# Sheet1.net
KiCad netlist of a schematic drawn in Altium Designer
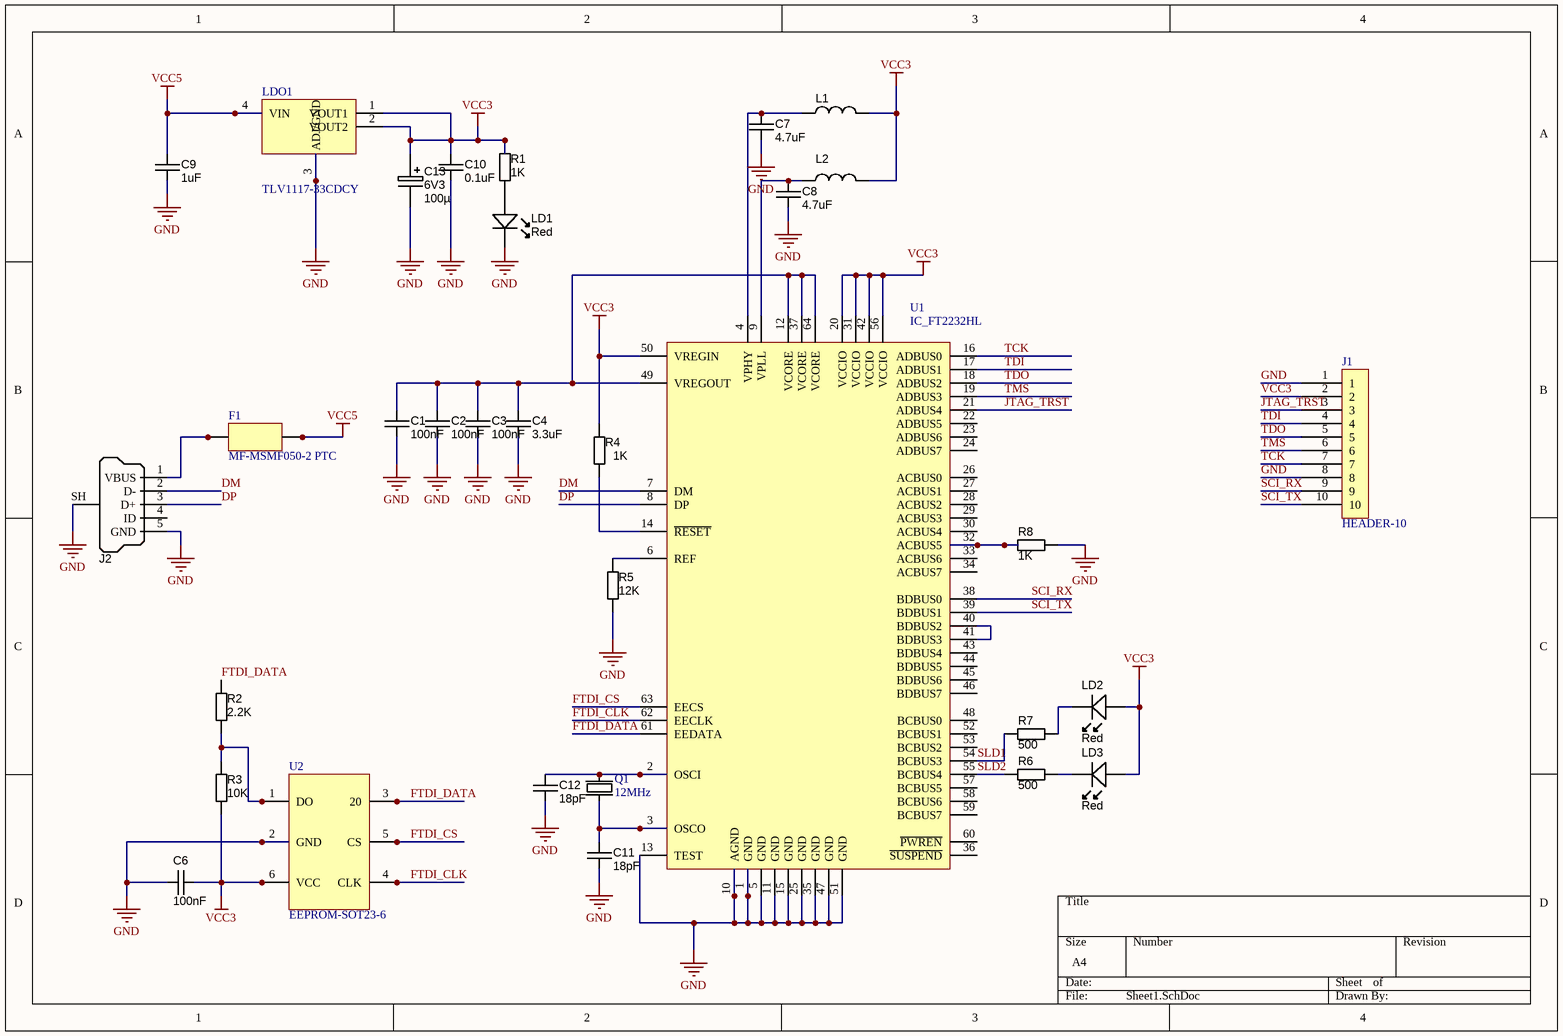
[diagram p0: Sheet1.SchDoc]

(export (version "E")
  (design (tool "Eeschema 10.0.6"))
  (components
    (comp (ref "C1")
      (value "100nF")
      (footprint "CAPC1608X90N")
      (description "Capacitor SMD Cer 39pF 1% 100V NP0 0603")
      (fields (field (name "TOLERANCE") "±1%"))
      (libsource (lib "PBL - Capacitors") (part "CAPC_39p_0603_NP0_100V_1%"))
    )
    (comp (ref "C2")
      (value "100nF")
      (footprint "CAPC1608X90N")
      (description "Capacitor SMD Cer 39pF 1% 100V NP0 0603")
      (fields (field (name "TOLERANCE") "±1%"))
      (libsource (lib "PBL - Capacitors") (part "CAPC_39p_0603_NP0_100V_1%"))
    )
    (comp (ref "C3")
      (value "100nF")
      (footprint "CAPC1608X90N")
      (description "Capacitor SMD Cer 39pF 1% 100V NP0 0603")
      (fields (field (name "TOLERANCE") "±1%"))
      (libsource (lib "PBL - Capacitors") (part "CAPC_39p_0603_NP0_100V_1%"))
    )
    (comp (ref "C4")
      (value "3.3uF")
      (footprint "CAPC1608X90N")
      (description "Capacitor SMD Cer 39pF 1% 100V NP0 0603")
      (fields (field (name "TOLERANCE") "±1%"))
      (libsource (lib "PBL - Capacitors") (part "CAPC_39p_0603_NP0_100V_1%"))
    )
    (comp (ref "C6")
      (value "100nF")
      (footprint "CAPC1608X90N")
      (description "Capacitor SMD Cer 39pF 1% 100V NP0 0603")
      (fields (field (name "TOLERANCE") "±1%"))
      (libsource (lib "PBL - Capacitors") (part "CAPC_39p_0603_NP0_100V_1%"))
    )
    (comp (ref "C7")
      (value "4.7uF")
      (footprint "CAPC1608X90N")
      (description "Capacitor SMD Cer 39pF 1% 100V NP0 0603")
      (fields (field (name "TOLERANCE") "±1%"))
      (libsource (lib "PBL - Capacitors") (part "CAPC_39p_0603_NP0_100V_1%"))
    )
    (comp (ref "C8")
      (value "4.7uF")
      (footprint "CAPC1608X90N")
      (description "Capacitor SMD Cer 39pF 1% 100V NP0 0603")
      (fields (field (name "TOLERANCE") "±1%"))
      (libsource (lib "PBL - Capacitors") (part "CAPC_39p_0603_NP0_100V_1%"))
    )
    (comp (ref "C9")
      (value "1uF")
      (footprint "CAPC1608X90N")
      (description "Capacitor SMD Cer 39pF 1% 100V NP0 0603")
      (fields (field (name "TOLERANCE") "±1%"))
      (libsource (lib "PBL - Capacitors") (part "CAPC_39p_0603_NP0_100V_1%"))
    )
    (comp (ref "C10")
      (value "0.1uF")
      (footprint "CAPC1608X90N")
      (description "Capacitor SMD Cer 39pF 1% 100V NP0 0603")
      (fields (field (name "TOLERANCE") "±1%"))
      (libsource (lib "PBL - Capacitors") (part "CAPC_39p_0603_NP0_100V_1%"))
    )
    (comp (ref "C11")
      (value "18pF")
      (footprint "CAPC1608X90N")
      (description "Capacitor SMD Cer 39pF 1% 100V NP0 0603")
      (fields (field (name "TOLERANCE") "±1%"))
      (libsource (lib "PBL - Capacitors") (part "CAPC_39p_0603_NP0_100V_1%"))
    )
    (comp (ref "C12")
      (value "18pF")
      (footprint "CAPC1608X90N")
      (description "Capacitor SMD Cer 39pF 1% 100V NP0 0603")
      (fields (field (name "TOLERANCE") "±1%"))
      (libsource (lib "PBL - Capacitors") (part "CAPC_39p_0603_NP0_100V_1%"))
    )
    (comp (ref "C13")
      (value "100µ")
      (footprint "CAPMP3528X210N")
      (description "Capacitor SMD Tantalum 100uF 20% 6.3V 1210")
      (fields (field (name "TOLERANCE") "±20%") (field (name "RATINGS") "6V3"))
      (libsource (lib "PBL - Capacitors") (part "CAPT_100u_1210_6V3"))
    )
    (comp (ref "F1")
      (value "MF-MSMF050-2 PTC")
      (footprint "PTC-1218")
      (libsource (lib "power") (part "MF-MSMF050-2 PTC"))
    )
    (comp (ref "J1")
      (value "HEADER-10")
      (footprint "MICRO-MATCH-10")
      (libsource (lib "connectors") (part "HEADER-10"))
    )
    (comp (ref "J2")
      (value "USB Micro Type B (recommended if hand soldering)")
      (footprint "USB_Micro-B_FCI_SMD")
      (description "Connector SMD-THD USB Micro Type B middle mount")
      (libsource (lib "PBL - Connectors") (part "USB_Micro_TypeB_FCI"))
    )
    (comp (ref "L1")
      (value "120R @ 100 MHz")
      (footprint "INDC1608N")
      (description "Ferrite bead 120 Ohm at 100 MHz 2A 0603 SMD")
      (libsource (lib "PBL - Inductors") (part "FERRITE_120R-100MHz_0603"))
    )
    (comp (ref "L2")
      (value "120R @ 100 MHz")
      (footprint "INDC1608N")
      (description "Ferrite bead 120 Ohm at 100 MHz 2A 0603 SMD")
      (libsource (lib "PBL - Inductors") (part "FERRITE_120R-100MHz_0603"))
    )
    (comp (ref "LD1")
      (value "Red")
      (footprint "LED-0603-RED")
      (description "LED 0603 SMD Hyper Red 630nm 220mcd 20mA")
      (libsource (lib "PBL - Light Sources") (part "LED_SMD_Red_0603_220mcd"))
    )
    (comp (ref "LD2")
      (value "Red")
      (footprint "LED-0603-RED")
      (description "LED 0603 SMD Hyper Red 630nm 220mcd 20mA")
      (libsource (lib "PBL - Light Sources") (part "LED_SMD_Red_0603_220mcd"))
    )
    (comp (ref "LD3")
      (value "Red")
      (footprint "LED-0603-RED")
      (description "LED 0603 SMD Hyper Red 630nm 220mcd 20mA")
      (libsource (lib "PBL - Light Sources") (part "LED_SMD_Red_0603_220mcd"))
    )
    (comp (ref "LDO1")
      (value "TLV1117-33CDCY")
      (footprint "SOT223")
      (libsource (lib "texas_instruments") (part "TLV1117-33CDCY"))
    )
    (comp (ref "Q1") (value "12MHz") (footprint "XTAL-5x3.2") (libsource (lib "misc") (part "XTAL_5x3.2")))
    (comp (ref "R1")
      (value "1K")
      (footprint "RESC1608X55N")
      (description "Resistor SMD chip 1k Ohm 0.1W 5% 0603")
      (fields (field (name "TOLERANCE") "±5%") (field (name "Comment") "Thick Film"))
      (libsource (lib "") (part "RES_1K_0603_5%_2"))
    )
    (comp (ref "R2")
      (value "2.2K")
      (footprint "RESC1608X55N")
      (description "Resistor SMD chip 1k Ohm 0.1W 5% 0603")
      (fields (field (name "TOLERANCE") "±5%") (field (name "Comment") "Thick Film"))
      (libsource (lib "") (part "RES_1K_0603_5%_2"))
    )
    (comp (ref "R3")
      (value "10K")
      (footprint "RESC1608X55N")
      (description "Resistor SMD chip 1k Ohm 0.1W 5% 0603")
      (fields (field (name "TOLERANCE") "±5%") (field (name "Comment") "Thick Film"))
      (libsource (lib "") (part "RES_1K_0603_5%_2"))
    )
    (comp (ref "R4")
      (value "1K")
      (footprint "RESC1608X55N")
      (description "Resistor SMD chip 1k Ohm 0.1W 5% 0603")
      (fields (field (name "TOLERANCE") "±5%"))
      (libsource (lib "") (part "RES_1K_0603_5%_1"))
    )
    (comp (ref "R5")
      (value "12K")
      (footprint "RESC1608X55N")
      (description "Resistor SMD chip 1k Ohm 0.1W 5% 0603")
      (fields (field (name "TOLERANCE") "±5%") (field (name "Comment") "Thick Film"))
      (libsource (lib "") (part "RES_1K_0603_5%_1"))
    )
    (comp (ref "R6")
      (value "500")
      (footprint "RESC1608X55N")
      (description "Resistor SMD chip 1k Ohm 0.1W 5% 0603")
      (fields (field (name "TOLERANCE") "±5%") (field (name "Comment") "Thick Film"))
      (libsource (lib "PBL - Resistors") (part "RES_1K_0603_5%"))
    )
    (comp (ref "R7")
      (value "500")
      (footprint "RESC1608X55N")
      (description "Resistor SMD chip 1k Ohm 0.1W 5% 0603")
      (fields (field (name "TOLERANCE") "±5%") (field (name "Comment") "Thick Film"))
      (libsource (lib "PBL - Resistors") (part "RES_1K_0603_5%"))
    )
    (comp (ref "R8")
      (value "1K")
      (footprint "RESC1608X55N")
      (description "Resistor SMD chip 1k Ohm 0.1W 5% 0603")
      (fields (field (name "TOLERANCE") "±5%") (field (name "Comment") "Thick Film"))
      (libsource (lib "PBL - Resistors") (part "RES_1K_0603_5%"))
    )
    (comp (ref "U1")
      (value "IC_FT2232HL")
      (footprint "LQFP-64")
      (description "Dual High Speed USB to Multipurpose UART/FIFO")
      (libsource (lib "FTDI_SCH_Public") (part "IC_FT2232HL"))
    )
    (comp (ref "U2")
      (value "EEPROM-SOT23-6")
      (footprint "SOT23-6-EEPROM")
      (libsource (lib "misc") (part "EEPROM-SOT23-6"))
    )
  )
  (nets
    (net (code "1") (name "/DM") (class "Default")
      (node (ref "J2") (pin "2") (pinfunction "D-_2") (pintype "passive"))
      (node (ref "U1") (pin "7") (pinfunction "DM_7") (pintype "passive"))
    )
    (net (code "2") (name "/DP") (class "Default")
      (node (ref "J2") (pin "3") (pinfunction "D+_3") (pintype "passive"))
      (node (ref "U1") (pin "8") (pinfunction "DP_8") (pintype "passive"))
    )
    (net (code "3") (name "/FTDI_CLK") (class "Default")
      (node (ref "U1") (pin "62") (pinfunction "EECLK_62") (pintype "passive"))
      (node (ref "U2") (pin "4") (pinfunction "CLK_4") (pintype "passive"))
    )
    (net (code "4") (name "/FTDI_CS") (class "Default")
      (node (ref "U1") (pin "63") (pinfunction "EECS_63") (pintype "passive"))
      (node (ref "U2") (pin "5") (pinfunction "CS_5") (pintype "passive"))
    )
    (net (code "5") (name "/FTDI_DATA") (class "Default")
      (node (ref "R2") (pin "1") (pinfunction "1_1") (pintype "passive"))
      (node (ref "U1") (pin "61") (pinfunction "EEDATA_61") (pintype "passive"))
      (node (ref "U2") (pin "3") (pinfunction "20_3") (pintype "passive"))
    )
    (net (code "6") (name "/JTAG_TRST") (class "Default")
      (node (ref "J1") (pin "3") (pinfunction "3_3") (pintype "passive"))
      (node (ref "U1") (pin "21") (pinfunction "ADBUS4_21") (pintype "passive"))
    )
    (net (code "7") (name "/SCI_RX") (class "Default")
      (node (ref "J1") (pin "9") (pinfunction "9_9") (pintype "passive"))
      (node (ref "U1") (pin "38") (pinfunction "BDBUS0_38") (pintype "passive"))
    )
    (net (code "8") (name "/SCI_TX") (class "Default")
      (node (ref "J1") (pin "10") (pinfunction "10_10") (pintype "passive"))
      (node (ref "U1") (pin "39") (pinfunction "BDBUS1_39") (pintype "passive"))
    )
    (net (code "9") (name "/SLD1") (class "Default")
      (node (ref "R7") (pin "2") (pinfunction "2_2") (pintype "passive"))
      (node (ref "U1") (pin "54") (pinfunction "BCBUS3_54") (pintype "passive"))
    )
    (net (code "10") (name "/SLD2") (class "Default")
      (node (ref "R6") (pin "2") (pinfunction "2_2") (pintype "passive"))
      (node (ref "U1") (pin "55") (pinfunction "BCBUS4_55") (pintype "passive"))
    )
    (net (code "11") (name "/TCK") (class "Default")
      (node (ref "J1") (pin "7") (pinfunction "7_7") (pintype "passive"))
      (node (ref "U1") (pin "16") (pinfunction "ADBUS0_16") (pintype "passive"))
    )
    (net (code "12") (name "/TDI") (class "Default")
      (node (ref "J1") (pin "4") (pinfunction "4_4") (pintype "passive"))
      (node (ref "U1") (pin "17") (pinfunction "ADBUS1_17") (pintype "passive"))
    )
    (net (code "13") (name "/TDO") (class "Default")
      (node (ref "J1") (pin "5") (pinfunction "5_5") (pintype "passive"))
      (node (ref "U1") (pin "18") (pinfunction "ADBUS2_18") (pintype "passive"))
    )
    (net (code "14") (name "/TMS") (class "Default")
      (node (ref "J1") (pin "6") (pinfunction "6_6") (pintype "passive"))
      (node (ref "U1") (pin "19") (pinfunction "ADBUS3_19") (pintype "passive"))
    )
    (net (code "15") (name "GND") (class "Default")
      (node (ref "C1") (pin "2") (pintype "passive"))
      (node (ref "C10") (pin "2") (pintype "passive"))
      (node (ref "C11") (pin "2") (pintype "passive"))
      (node (ref "C12") (pin "1") (pintype "passive"))
      (node (ref "C13") (pin "2") (pintype "passive"))
      (node (ref "C2") (pin "2") (pintype "passive"))
      (node (ref "C3") (pin "2") (pintype "passive"))
      (node (ref "C4") (pin "2") (pintype "passive"))
      (node (ref "C6") (pin "1") (pintype "passive"))
      (node (ref "C7") (pin "2") (pintype "passive"))
      (node (ref "C8") (pin "2") (pintype "passive"))
      (node (ref "C9") (pin "2") (pintype "passive"))
      (node (ref "J1") (pin "1") (pinfunction "1_1") (pintype "passive"))
      (node (ref "J1") (pin "8") (pinfunction "8_8") (pintype "passive"))
      (node (ref "J2") (pin "5") (pinfunction "GND_5") (pintype "passive"))
      (node (ref "J2") (pin "SH") (pinfunction "Shell_SH") (pintype "passive"))
      (node (ref "LD1") (pin "K") (pinfunction "K_K") (pintype "passive"))
      (node (ref "LDO1") (pin "3") (pinfunction "ADJ/GND_3") (pintype "passive"))
      (node (ref "R5") (pin "1") (pinfunction "1_1") (pintype "passive"))
      (node (ref "R8") (pin "1") (pinfunction "1_1") (pintype "passive"))
      (node (ref "U1") (pin "1") (pinfunction "GND_1") (pintype "passive"))
      (node (ref "U1") (pin "10") (pinfunction "AGND_10") (pintype "passive"))
      (node (ref "U1") (pin "11") (pinfunction "GND_11") (pintype "passive"))
      (node (ref "U1") (pin "13") (pinfunction "TEST_13") (pintype "passive"))
      (node (ref "U1") (pin "15") (pinfunction "GND_15") (pintype "passive"))
      (node (ref "U1") (pin "25") (pinfunction "GND_25") (pintype "passive"))
      (node (ref "U1") (pin "35") (pinfunction "GND_35") (pintype "passive"))
      (node (ref "U1") (pin "47") (pinfunction "GND_47") (pintype "passive"))
      (node (ref "U1") (pin "5") (pinfunction "GND_5") (pintype "passive"))
      (node (ref "U1") (pin "51") (pinfunction "GND_51") (pintype "passive"))
      (node (ref "U2") (pin "2") (pinfunction "GND_2") (pintype "passive"))
    )
    (net (code "16") (name "Net-(F1-1)") (class "Default")
      (node (ref "F1") (pin "21") (pinfunction "1_21") (pintype "passive"))
      (node (ref "J2") (pin "1") (pinfunction "VBUS_1") (pintype "passive"))
    )
    (net (code "17") (name "Net-(LD1-PadA)") (class "Default")
      (node (ref "LD1") (pin "A") (pinfunction "A_A") (pintype "passive"))
      (node (ref "R1") (pin "2") (pinfunction "2_2") (pintype "passive"))
    )
    (net (code "18") (name "Net-(LD2-PadK)") (class "Default")
      (node (ref "LD2") (pin "K") (pinfunction "K_K") (pintype "passive"))
      (node (ref "R7") (pin "1") (pinfunction "1_1") (pintype "passive"))
    )
    (net (code "19") (name "Net-(LD3-PadK)") (class "Default")
      (node (ref "LD3") (pin "K") (pinfunction "K_K") (pintype "passive"))
      (node (ref "R6") (pin "1") (pinfunction "1_1") (pintype "passive"))
    )
    (net (code "20") (name "Net-(U1-ACBUS5)") (class "Default")
      (node (ref "R8") (pin "2") (pinfunction "2_2") (pintype "passive"))
      (node (ref "U1") (pin "32") (pinfunction "ACBUS5_32") (pintype "passive"))
    )
    (net (code "21") (name "Net-(U1-BDBUS2)") (class "Default")
      (node (ref "U1") (pin "40") (pinfunction "BDBUS2_40") (pintype "passive"))
      (node (ref "U1") (pin "41") (pinfunction "BDBUS3_41") (pintype "passive"))
    )
    (net (code "22") (name "Net-(U1-OSCI)") (class "Default")
      (node (ref "C12") (pin "2") (pintype "passive"))
      (node (ref "Q1") (pin "2") (pinfunction "2_2") (pintype "passive"))
      (node (ref "U1") (pin "2") (pinfunction "OSCI_2") (pintype "passive"))
    )
    (net (code "23") (name "Net-(U1-OSCO)") (class "Default")
      (node (ref "C11") (pin "1") (pintype "passive"))
      (node (ref "Q1") (pin "1") (pinfunction "1_1") (pintype "passive"))
      (node (ref "U1") (pin "3") (pinfunction "OSCO_3") (pintype "passive"))
    )
    (net (code "24") (name "Net-(U1-REF)") (class "Default")
      (node (ref "R5") (pin "2") (pinfunction "2_2") (pintype "passive"))
      (node (ref "U1") (pin "6") (pinfunction "REF_6") (pintype "passive"))
    )
    (net (code "25") (name "Net-(U1-VPHY)") (class "Default")
      (node (ref "C7") (pin "1") (pintype "passive"))
      (node (ref "L1") (pin "1") (pinfunction "1_1") (pintype "passive"))
      (node (ref "U1") (pin "4") (pinfunction "VPHY_4") (pintype "passive"))
    )
    (net (code "26") (name "Net-(U1-VPLL)") (class "Default")
      (node (ref "C8") (pin "1") (pintype "passive"))
      (node (ref "L2") (pin "1") (pinfunction "1_1") (pintype "passive"))
      (node (ref "U1") (pin "9") (pinfunction "VPLL_9") (pintype "passive"))
    )
    (net (code "27") (name "Net-(U1-VREGOUT)") (class "Default")
      (node (ref "C1") (pin "1") (pintype "passive"))
      (node (ref "C2") (pin "1") (pintype "passive"))
      (node (ref "C3") (pin "1") (pintype "passive"))
      (node (ref "C4") (pin "1") (pintype "passive"))
      (node (ref "U1") (pin "12") (pinfunction "VCORE_12") (pintype "passive"))
      (node (ref "U1") (pin "37") (pinfunction "VCORE_37") (pintype "passive"))
      (node (ref "U1") (pin "49") (pinfunction "VREGOUT_49") (pintype "passive"))
      (node (ref "U1") (pin "64") (pinfunction "VCORE_64") (pintype "passive"))
    )
    (net (code "28") (name "Net-(U1-~{RESET})") (class "Default")
      (node (ref "R4") (pin "1") (pinfunction "1_1") (pintype "passive"))
      (node (ref "U1") (pin "14") (pinfunction "~{RESET}_14") (pintype "passive"))
    )
    (net (code "29") (name "Net-(U2-DO)") (class "Default")
      (node (ref "R2") (pin "2") (pinfunction "2_2") (pintype "passive"))
      (node (ref "R3") (pin "1") (pinfunction "1_1") (pintype "passive"))
      (node (ref "U2") (pin "1") (pinfunction "DO_1") (pintype "passive"))
    )
    (net (code "30") (name "VCC3") (class "Default")
      (node (ref "C10") (pin "1") (pintype "passive"))
      (node (ref "C13") (pin "1") (pintype "passive"))
      (node (ref "C6") (pin "2") (pintype "passive"))
      (node (ref "J1") (pin "2") (pinfunction "2_2") (pintype "passive"))
      (node (ref "L1") (pin "2") (pinfunction "2_2") (pintype "passive"))
      (node (ref "L2") (pin "2") (pinfunction "2_2") (pintype "passive"))
      (node (ref "LD2") (pin "A") (pinfunction "A_A") (pintype "passive"))
      (node (ref "LD3") (pin "A") (pinfunction "A_A") (pintype "passive"))
      (node (ref "LDO1") (pin "1") (pinfunction "VOUT1_1") (pintype "passive"))
      (node (ref "LDO1") (pin "2") (pinfunction "VOUT2_2") (pintype "passive"))
      (node (ref "R1") (pin "1") (pinfunction "1_1") (pintype "passive"))
      (node (ref "R3") (pin "2") (pinfunction "2_2") (pintype "passive"))
      (node (ref "R4") (pin "2") (pinfunction "2_2") (pintype "passive"))
      (node (ref "U1") (pin "20") (pinfunction "VCCIO_20") (pintype "passive"))
      (node (ref "U1") (pin "31") (pinfunction "VCCIO_31") (pintype "passive"))
      (node (ref "U1") (pin "42") (pinfunction "VCCIO_42") (pintype "passive"))
      (node (ref "U1") (pin "50") (pinfunction "VREGIN_50") (pintype "passive"))
      (node (ref "U1") (pin "56") (pinfunction "VCCIO_56") (pintype "passive"))
      (node (ref "U2") (pin "6") (pinfunction "VCC_6") (pintype "passive"))
    )
    (net (code "31") (name "VCC5") (class "Default")
      (node (ref "C9") (pin "1") (pintype "passive"))
      (node (ref "F1") (pin "22") (pinfunction "2_22") (pintype "passive"))
      (node (ref "LDO1") (pin "4") (pinfunction "VIN_4") (pintype "passive"))
    )
    (net (code "32") (name "unconnected-(J2-ID-Pad4)") (class "Default")
      (node (ref "J2") (pin "4") (pinfunction "ID_4") (pintype "passive"))
    )
    (net (code "33") (name "unconnected-(U1-ACBUS0-Pad26)") (class "Default")
      (node (ref "U1") (pin "26") (pinfunction "ACBUS0_26") (pintype "passive"))
    )
    (net (code "34") (name "unconnected-(U1-ACBUS1-Pad27)") (class "Default")
      (node (ref "U1") (pin "27") (pinfunction "ACBUS1_27") (pintype "passive"))
    )
    (net (code "35") (name "unconnected-(U1-ACBUS2-Pad28)") (class "Default")
      (node (ref "U1") (pin "28") (pinfunction "ACBUS2_28") (pintype "passive"))
    )
    (net (code "36") (name "unconnected-(U1-ACBUS3-Pad29)") (class "Default")
      (node (ref "U1") (pin "29") (pinfunction "ACBUS3_29") (pintype "passive"))
    )
    (net (code "37") (name "unconnected-(U1-ACBUS4-Pad30)") (class "Default")
      (node (ref "U1") (pin "30") (pinfunction "ACBUS4_30") (pintype "passive"))
    )
    (net (code "38") (name "unconnected-(U1-ACBUS6-Pad33)") (class "Default")
      (node (ref "U1") (pin "33") (pinfunction "ACBUS6_33") (pintype "passive"))
    )
    (net (code "39") (name "unconnected-(U1-ACBUS7-Pad34)") (class "Default")
      (node (ref "U1") (pin "34") (pinfunction "ACBUS7_34") (pintype "passive"))
    )
    (net (code "40") (name "unconnected-(U1-ADBUS5-Pad22)") (class "Default")
      (node (ref "U1") (pin "22") (pinfunction "ADBUS5_22") (pintype "passive"))
    )
    (net (code "41") (name "unconnected-(U1-ADBUS6-Pad23)") (class "Default")
      (node (ref "U1") (pin "23") (pinfunction "ADBUS6_23") (pintype "passive"))
    )
    (net (code "42") (name "unconnected-(U1-ADBUS7-Pad24)") (class "Default")
      (node (ref "U1") (pin "24") (pinfunction "ADBUS7_24") (pintype "passive"))
    )
    (net (code "43") (name "unconnected-(U1-BCBUS0-Pad48)") (class "Default")
      (node (ref "U1") (pin "48") (pinfunction "BCBUS0_48") (pintype "passive"))
    )
    (net (code "44") (name "unconnected-(U1-BCBUS1-Pad52)") (class "Default")
      (node (ref "U1") (pin "52") (pinfunction "BCBUS1_52") (pintype "passive"))
    )
    (net (code "45") (name "unconnected-(U1-BCBUS2-Pad53)") (class "Default")
      (node (ref "U1") (pin "53") (pinfunction "BCBUS2_53") (pintype "passive"))
    )
    (net (code "46") (name "unconnected-(U1-BCBUS5-Pad57)") (class "Default")
      (node (ref "U1") (pin "57") (pinfunction "BCBUS5_57") (pintype "passive"))
    )
    (net (code "47") (name "unconnected-(U1-BCBUS6-Pad58)") (class "Default")
      (node (ref "U1") (pin "58") (pinfunction "BCBUS6_58") (pintype "passive"))
    )
    (net (code "48") (name "unconnected-(U1-BCBUS7-Pad59)") (class "Default")
      (node (ref "U1") (pin "59") (pinfunction "BCBUS7_59") (pintype "passive"))
    )
    (net (code "49") (name "unconnected-(U1-BDBUS4-Pad43)") (class "Default")
      (node (ref "U1") (pin "43") (pinfunction "BDBUS4_43") (pintype "passive"))
    )
    (net (code "50") (name "unconnected-(U1-BDBUS5-Pad44)") (class "Default")
      (node (ref "U1") (pin "44") (pinfunction "BDBUS5_44") (pintype "passive"))
    )
    (net (code "51") (name "unconnected-(U1-BDBUS6-Pad45)") (class "Default")
      (node (ref "U1") (pin "45") (pinfunction "BDBUS6_45") (pintype "passive"))
    )
    (net (code "52") (name "unconnected-(U1-BDBUS7-Pad46)") (class "Default")
      (node (ref "U1") (pin "46") (pinfunction "BDBUS7_46") (pintype "passive"))
    )
    (net (code "53") (name "unconnected-(U1-~{PWREN}-Pad60)") (class "Default")
      (node (ref "U1") (pin "60") (pinfunction "~{PWREN}_60") (pintype "passive"))
    )
    (net (code "54") (name "unconnected-(U1-~{SUSPEND}-Pad36)") (class "Default")
      (node (ref "U1") (pin "36") (pinfunction "~{SUSPEND}_36") (pintype "passive"))
    )
  )
)
